# schematic.net
KiCad netlist of a schematic drawn in EasyEDA
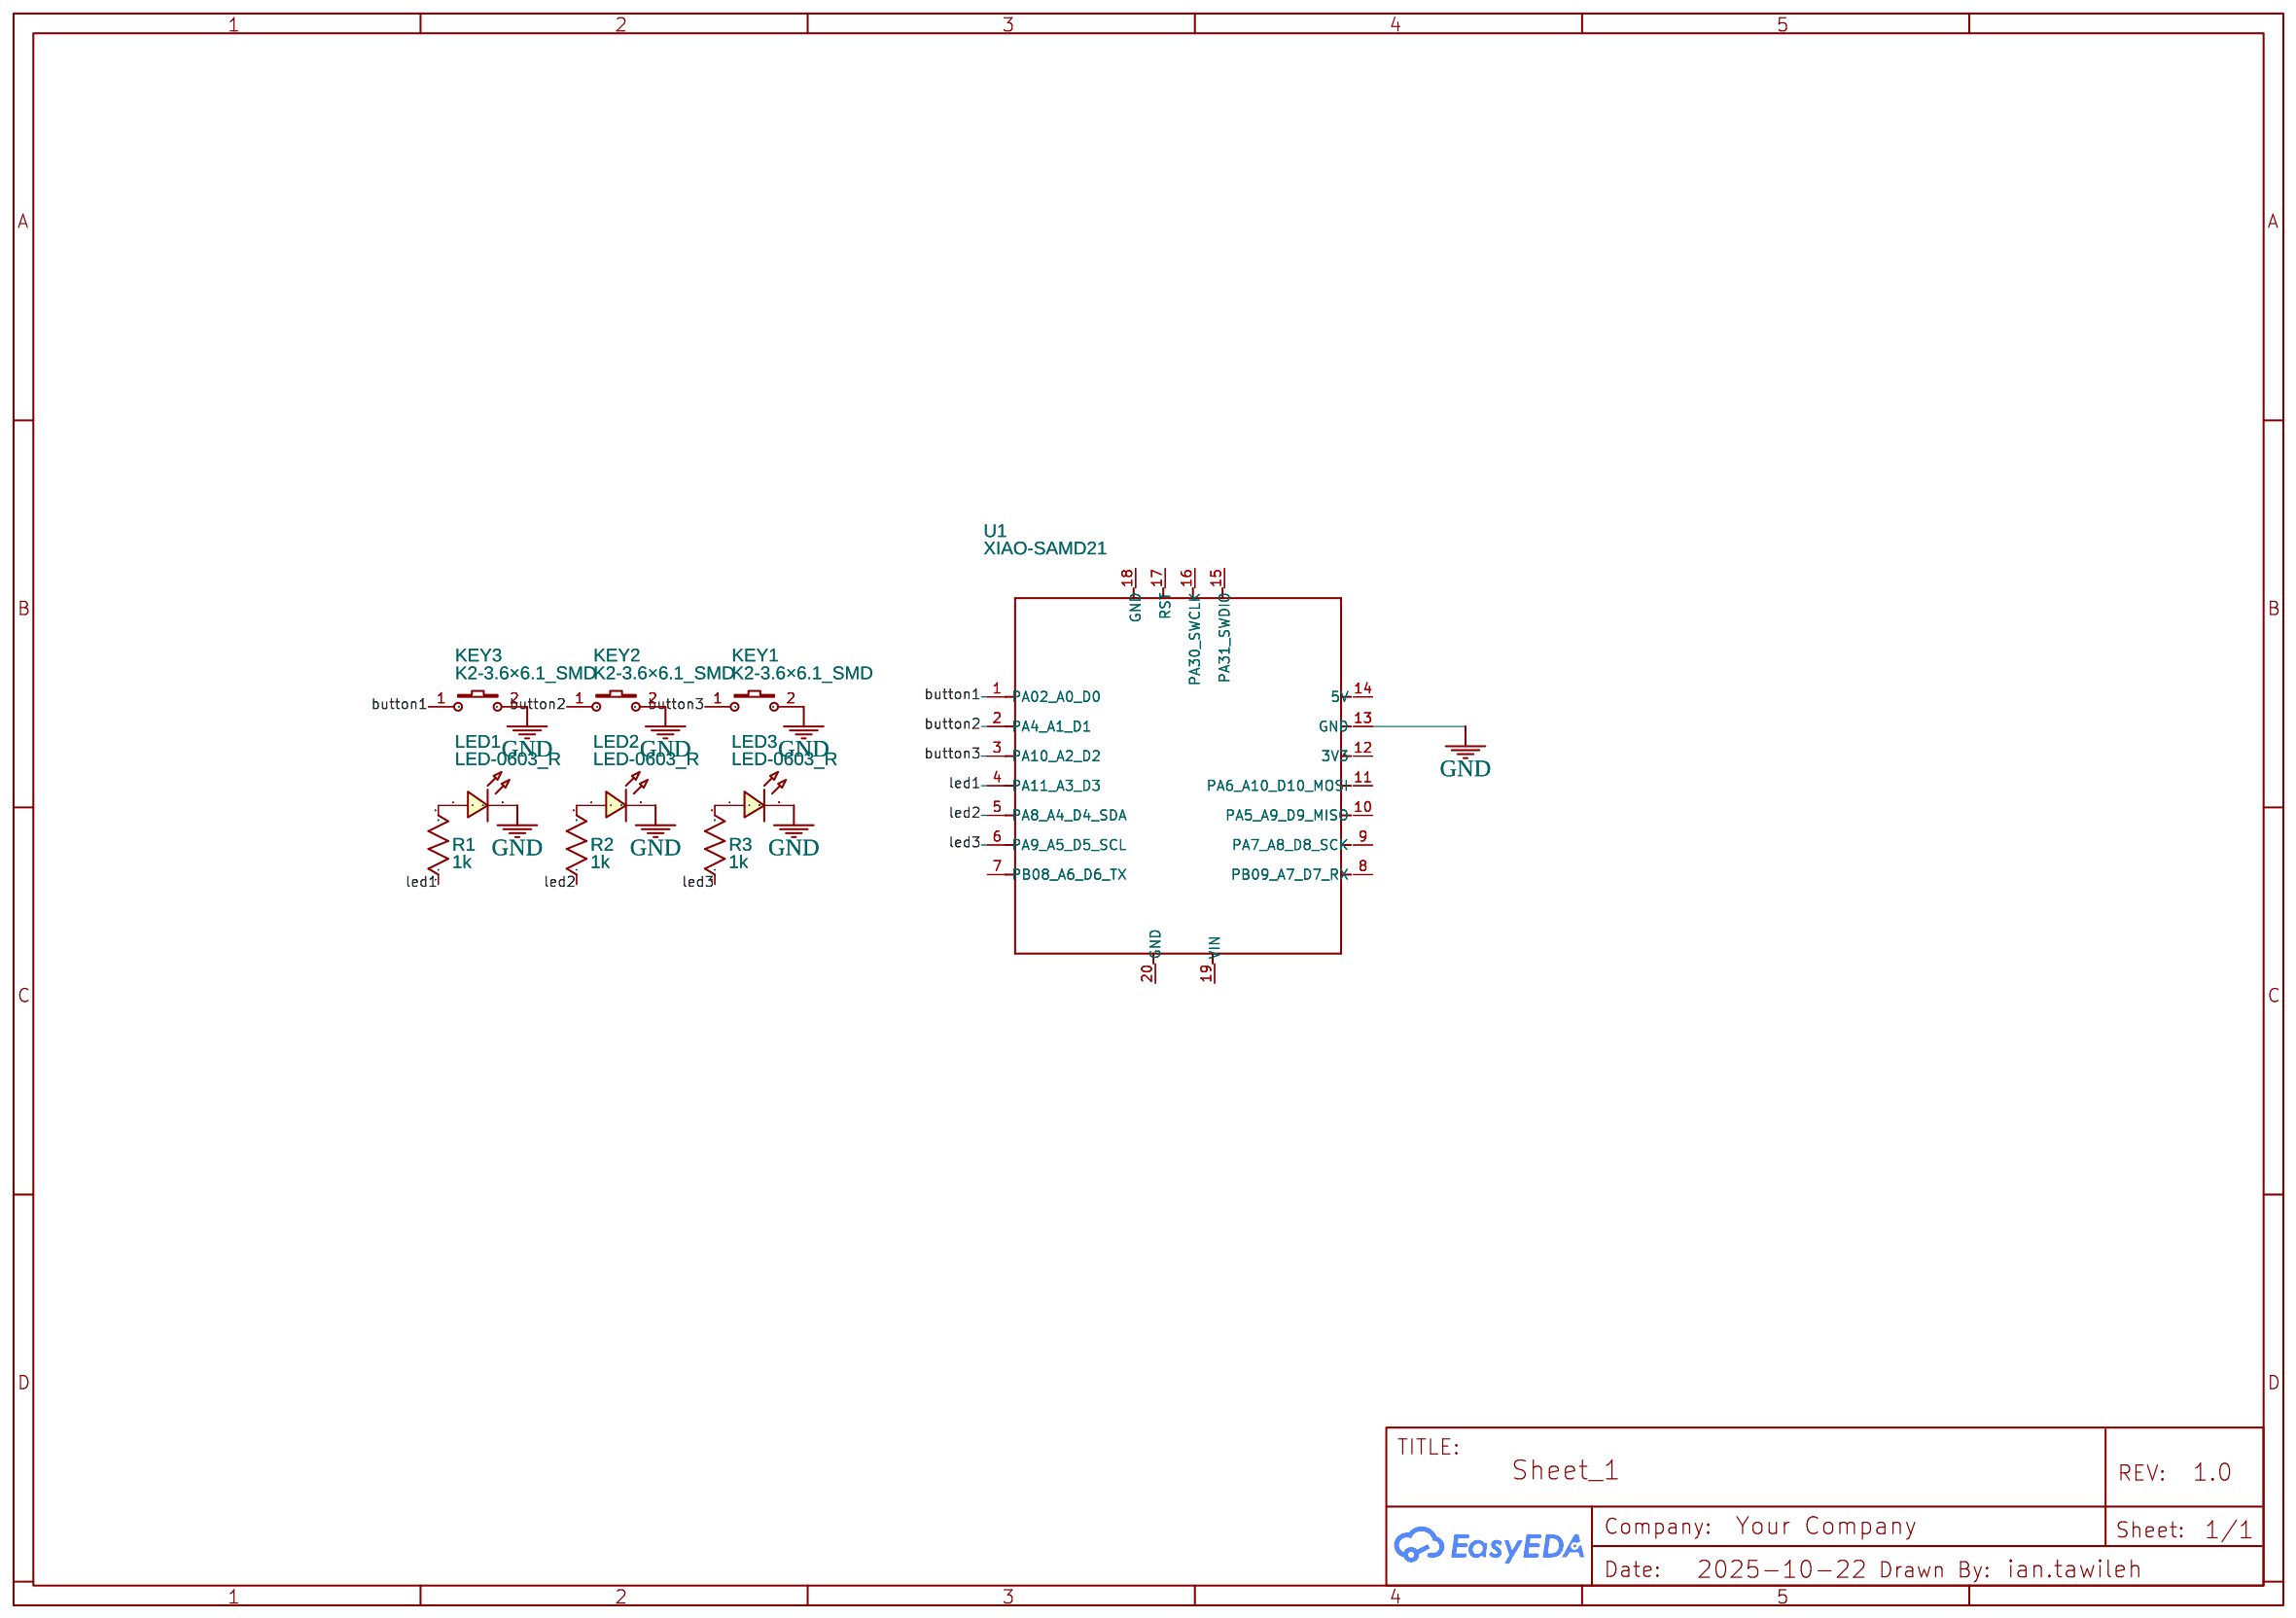
[diagram p0: schematic sheet]

(export (version "E")
  (design (tool "Eeschema 10.0.6"))
  (components
    (comp (ref "KEY1")
      (value "K2-3.6×6.1_SMD")
      (fields (field (name "Manufacturer Part") "K2-1107ST-A4SW-06"))
      (libsource (lib "") (part "K2-3.6×6.1_SMD"))
    )
    (comp (ref "KEY2")
      (value "K2-3.6×6.1_SMD")
      (fields (field (name "Manufacturer Part") "K2-1107ST-A4SW-06"))
      (libsource (lib "") (part "K2-3.6×6.1_SMD"))
    )
    (comp (ref "KEY3")
      (value "K2-3.6×6.1_SMD")
      (fields (field (name "Manufacturer Part") "K2-1107ST-A4SW-06"))
      (libsource (lib "") (part "K2-3.6×6.1_SMD"))
    )
    (comp (ref "LED1")
      (value "LED-0603_R")
      (fields
        (field (name "Manufacturer Part") "19-217/R6C-AL1M2VY/3T")
        (field (name "Manufacturer") "EVERLIGHT(台湾亿光)")
      )
      (libsource (lib "") (part "LED-0603_R"))
    )
    (comp (ref "LED2")
      (value "LED-0603_R")
      (fields
        (field (name "Manufacturer Part") "19-217/R6C-AL1M2VY/3T")
        (field (name "Manufacturer") "EVERLIGHT(台湾亿光)")
      )
      (libsource (lib "") (part "LED-0603_R"))
    )
    (comp (ref "LED3")
      (value "LED-0603_R")
      (fields
        (field (name "Manufacturer Part") "19-217/R6C-AL1M2VY/3T")
        (field (name "Manufacturer") "EVERLIGHT(台湾亿光)")
      )
      (libsource (lib "") (part "LED-0603_R"))
    )
    (comp (ref "R1") (value "1k") (libsource (lib "") (part "R_0603_US")))
    (comp (ref "R2") (value "1k") (libsource (lib "") (part "R_0603_US")))
    (comp (ref "R3") (value "1k") (libsource (lib "") (part "R_0603_US")))
    (comp (ref "U1") (value "XIAO-SAMD21") (libsource (lib "") (part "XIAO-SAMD21")))
  )
  (nets
    (net (code "1") (name "/button1") (class "Default")
      (node (ref "KEY3") (pin "1") (pinfunction "1_1") (pintype "unspecified"))
      (node (ref "U1") (pin "1") (pinfunction "PA02_A0_D0_1") (pintype "bidirectional"))
    )
    (net (code "2") (name "/button2") (class "Default")
      (node (ref "KEY2") (pin "1") (pinfunction "1_1") (pintype "unspecified"))
      (node (ref "U1") (pin "2") (pinfunction "PA4_A1_D1_2") (pintype "bidirectional"))
    )
    (net (code "3") (name "/button3") (class "Default")
      (node (ref "KEY1") (pin "1") (pinfunction "1_1") (pintype "unspecified"))
      (node (ref "U1") (pin "3") (pinfunction "PA10_A2_D2_3") (pintype "bidirectional"))
    )
    (net (code "4") (name "/led1") (class "Default")
      (node (ref "R1") (pin "1") (pinfunction "1_1") (pintype "unspecified"))
      (node (ref "U1") (pin "4") (pinfunction "PA11_A3_D3_4") (pintype "bidirectional"))
    )
    (net (code "5") (name "/led2") (class "Default")
      (node (ref "R2") (pin "1") (pinfunction "1_1") (pintype "unspecified"))
      (node (ref "U1") (pin "5") (pinfunction "PA8_A4_D4_SDA_5") (pintype "bidirectional"))
    )
    (net (code "6") (name "/led3") (class "Default")
      (node (ref "R3") (pin "1") (pinfunction "1_1") (pintype "unspecified"))
      (node (ref "U1") (pin "6") (pinfunction "PA9_A5_D5_SCL_6") (pintype "bidirectional"))
    )
    (net (code "7") (name "GND") (class "Default")
      (node (ref "KEY1") (pin "2") (pinfunction "2_2") (pintype "unspecified"))
      (node (ref "KEY2") (pin "2") (pinfunction "2_2") (pintype "unspecified"))
      (node (ref "KEY3") (pin "2") (pinfunction "2_2") (pintype "unspecified"))
      (node (ref "LED1") (pin "2") (pinfunction "2_2") (pintype "unspecified"))
      (node (ref "LED2") (pin "2") (pinfunction "2_2") (pintype "unspecified"))
      (node (ref "LED3") (pin "2") (pinfunction "2_2") (pintype "unspecified"))
      (node (ref "U1") (pin "13") (pinfunction "GND_13") (pintype "bidirectional"))
    )
    (net (code "8") (name "Net-(LED1-Pad1)") (class "Default")
      (node (ref "LED1") (pin "1") (pinfunction "1_1") (pintype "unspecified"))
      (node (ref "R1") (pin "2") (pinfunction "2_2") (pintype "unspecified"))
    )
    (net (code "9") (name "Net-(LED2-Pad1)") (class "Default")
      (node (ref "LED2") (pin "1") (pinfunction "1_1") (pintype "unspecified"))
      (node (ref "R2") (pin "2") (pinfunction "2_2") (pintype "unspecified"))
    )
    (net (code "10") (name "Net-(LED3-Pad1)") (class "Default")
      (node (ref "LED3") (pin "1") (pinfunction "1_1") (pintype "unspecified"))
      (node (ref "R3") (pin "2") (pinfunction "2_2") (pintype "unspecified"))
    )
    (net (code "11") (name "unconnected-(U1-3V3-Pad12)") (class "Default")
      (node (ref "U1") (pin "12") (pinfunction "3V3_12") (pintype "bidirectional"))
    )
    (net (code "12") (name "unconnected-(U1-5V-Pad14)") (class "Default")
      (node (ref "U1") (pin "14") (pinfunction "5V_14") (pintype "bidirectional"))
    )
    (net (code "13") (name "unconnected-(U1-GND-Pad18)") (class "Default")
      (node (ref "U1") (pin "18") (pinfunction "GND_18") (pintype "bidirectional"))
    )
    (net (code "14") (name "unconnected-(U1-GND-Pad20)") (class "Default")
      (node (ref "U1") (pin "20") (pinfunction "GND_20") (pintype "bidirectional"))
    )
    (net (code "15") (name "unconnected-(U1-PA5_A9_D9_MISO-Pad10)") (class "Default")
      (node (ref "U1") (pin "10") (pinfunction "PA5_A9_D9_MISO_10") (pintype "bidirectional"))
    )
    (net (code "16") (name "unconnected-(U1-PA6_A10_D10_MOSI-Pad11)") (class "Default")
      (node (ref "U1") (pin "11") (pinfunction "PA6_A10_D10_MOSI_11") (pintype "bidirectional"))
    )
    (net (code "17") (name "unconnected-(U1-PA7_A8_D8_SCK-Pad9)") (class "Default")
      (node (ref "U1") (pin "9") (pinfunction "PA7_A8_D8_SCK_9") (pintype "bidirectional"))
    )
    (net (code "18") (name "unconnected-(U1-PA30_SWCLK-Pad16)") (class "Default")
      (node (ref "U1") (pin "16") (pinfunction "PA30_SWCLK_16") (pintype "bidirectional"))
    )
    (net (code "19") (name "unconnected-(U1-PA31_SWDIO-Pad15)") (class "Default")
      (node (ref "U1") (pin "15") (pinfunction "PA31_SWDIO_15") (pintype "bidirectional"))
    )
    (net (code "20") (name "unconnected-(U1-PB08_A6_D6_TX-Pad7)") (class "Default")
      (node (ref "U1") (pin "7") (pinfunction "PB08_A6_D6_TX_7") (pintype "bidirectional"))
    )
    (net (code "21") (name "unconnected-(U1-PB09_A7_D7_RX-Pad8)") (class "Default")
      (node (ref "U1") (pin "8") (pinfunction "PB09_A7_D7_RX_8") (pintype "bidirectional"))
    )
    (net (code "22") (name "unconnected-(U1-RST-Pad17)") (class "Default")
      (node (ref "U1") (pin "17") (pinfunction "RST_17") (pintype "bidirectional"))
    )
    (net (code "23") (name "unconnected-(U1-VIN-Pad19)") (class "Default")
      (node (ref "U1") (pin "19") (pinfunction "VIN_19") (pintype "bidirectional"))
    )
  )
)
